# Coax_Encoder.net
KiCad netlist of a schematic drawn in EAGLE
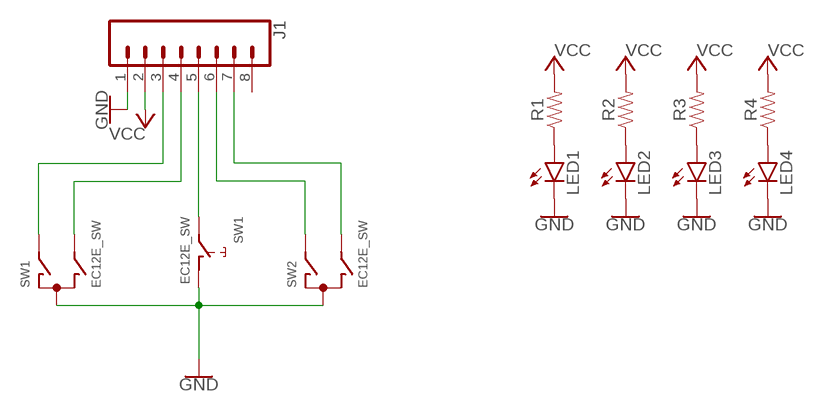
[diagram p0: schematic, sheet 1]

(export (version "E")
  (design (tool "Eeschema 10.0.6"))
  (components
    (comp (ref "J1")
      (value "CONN_08\"")
      (footprint "eagle-import:1X08")
      (libsource (lib "eagle-import") (part "CONN_08{dblquote}"))
    )
    (comp (ref "LED1")
      (value "LED3MM")
      (footprint "eagle-import:LED3MM")
      (libsource (lib "eagle-import") (part "LED3MM"))
    )
    (comp (ref "LED2")
      (value "LED3MM")
      (footprint "eagle-import:LED3MM")
      (libsource (lib "eagle-import") (part "LED3MM"))
    )
    (comp (ref "LED3")
      (value "LED3MM")
      (footprint "eagle-import:LED3MM")
      (libsource (lib "eagle-import") (part "LED3MM"))
    )
    (comp (ref "LED4")
      (value "LED3MM")
      (footprint "eagle-import:LED3MM")
      (libsource (lib "eagle-import") (part "LED3MM"))
    )
    (comp (ref "R1")
      (value "RESISTOR1206")
      (footprint "eagle-import:1206")
      (libsource (lib "eagle-import") (part "RESISTOR1206"))
    )
    (comp (ref "R2")
      (value "RESISTOR1206")
      (footprint "eagle-import:1206")
      (libsource (lib "eagle-import") (part "RESISTOR1206"))
    )
    (comp (ref "R3")
      (value "RESISTOR1206")
      (footprint "eagle-import:1206")
      (libsource (lib "eagle-import") (part "RESISTOR1206"))
    )
    (comp (ref "R4")
      (value "RESISTOR1206")
      (footprint "eagle-import:1206")
      (libsource (lib "eagle-import") (part "RESISTOR1206"))
    )
    (comp (ref "SW1")
      (value "EC12E_SW")
      (footprint "eagle-import:ALPS_EC12E_SW")
      (fields (field (name "MPN") "EC12E2424407"))
      (libsource (lib "eagle-import") (part "EC12E_SW"))
    )
    (comp (ref "SW2")
      (value "EC12E_SW")
      (footprint "eagle-import:ALPS_EC12E_SW")
      (fields (field (name "MPN") "EC12E2424407"))
      (libsource (lib "eagle-import") (part "EC12E_SW"))
    )
  )
  (nets
    (net (code "1") (name "GND") (class "Default")
      (node (ref "J1") (pin "1") (pinfunction "1_1") (pintype "passive"))
      (node (ref "LED1") (pin "K") (pinfunction "C_K") (pintype "passive"))
      (node (ref "LED2") (pin "K") (pinfunction "C_K") (pintype "passive"))
      (node (ref "LED3") (pin "K") (pinfunction "C_K") (pintype "passive"))
      (node (ref "LED4") (pin "K") (pinfunction "C_K") (pintype "passive"))
      (node (ref "SW1") (pin "C") (pinfunction "C_C") (pintype "passive"))
      (node (ref "SW1") (pin "D") (pinfunction "1_D") (pintype "passive"))
      (node (ref "SW2") (pin "C") (pinfunction "C_C") (pintype "passive"))
    )
    (net (code "2") (name "Net-(J1-Pad3)") (class "Default")
      (node (ref "J1") (pin "3") (pinfunction "3_3") (pintype "passive"))
      (node (ref "SW1") (pin "A") (pinfunction "A_A") (pintype "passive"))
    )
    (net (code "3") (name "Net-(J1-Pad4)") (class "Default")
      (node (ref "J1") (pin "4") (pinfunction "4_4") (pintype "passive"))
      (node (ref "SW1") (pin "B") (pinfunction "B_B") (pintype "passive"))
    )
    (net (code "4") (name "Net-(J1-Pad6)") (class "Default")
      (node (ref "J1") (pin "6") (pinfunction "6_6") (pintype "passive"))
      (node (ref "SW2") (pin "A") (pinfunction "A_A") (pintype "passive"))
    )
    (net (code "5") (name "Net-(J1-Pad7)") (class "Default")
      (node (ref "J1") (pin "7") (pinfunction "7_7") (pintype "passive"))
      (node (ref "SW2") (pin "B") (pinfunction "B_B") (pintype "passive"))
    )
    (net (code "6") (name "Net-(LED1-PadA)") (class "Default")
      (node (ref "LED1") (pin "A") (pinfunction "A_A") (pintype "passive"))
      (node (ref "R1") (pin "1") (pinfunction "1_1") (pintype "passive"))
    )
    (net (code "7") (name "Net-(LED2-PadA)") (class "Default")
      (node (ref "LED2") (pin "A") (pinfunction "A_A") (pintype "passive"))
      (node (ref "R2") (pin "1") (pinfunction "1_1") (pintype "passive"))
    )
    (net (code "8") (name "Net-(LED3-PadA)") (class "Default")
      (node (ref "LED3") (pin "A") (pinfunction "A_A") (pintype "passive"))
      (node (ref "R3") (pin "1") (pinfunction "1_1") (pintype "passive"))
    )
    (net (code "9") (name "Net-(LED4-PadA)") (class "Default")
      (node (ref "LED4") (pin "A") (pinfunction "A_A") (pintype "passive"))
      (node (ref "R4") (pin "1") (pinfunction "1_1") (pintype "passive"))
    )
    (net (code "10") (name "Net-(SW1B-2)") (class "Default")
      (node (ref "J1") (pin "5") (pinfunction "5_5") (pintype "passive"))
      (node (ref "SW1") (pin "E") (pinfunction "2_E") (pintype "passive"))
    )
    (net (code "11") (name "VCC") (class "Default")
      (node (ref "J1") (pin "2") (pinfunction "2_2") (pintype "passive"))
      (node (ref "R1") (pin "2") (pinfunction "2_2") (pintype "passive"))
      (node (ref "R2") (pin "2") (pinfunction "2_2") (pintype "passive"))
      (node (ref "R3") (pin "2") (pinfunction "2_2") (pintype "passive"))
      (node (ref "R4") (pin "2") (pinfunction "2_2") (pintype "passive"))
    )
    (net (code "12") (name "unconnected-(J1-Pad8)") (class "Default")
      (node (ref "J1") (pin "8") (pinfunction "8_8") (pintype "passive"))
    )
  )
)
